# board.net
KiCad netlist of a schematic drawn in EAGLE
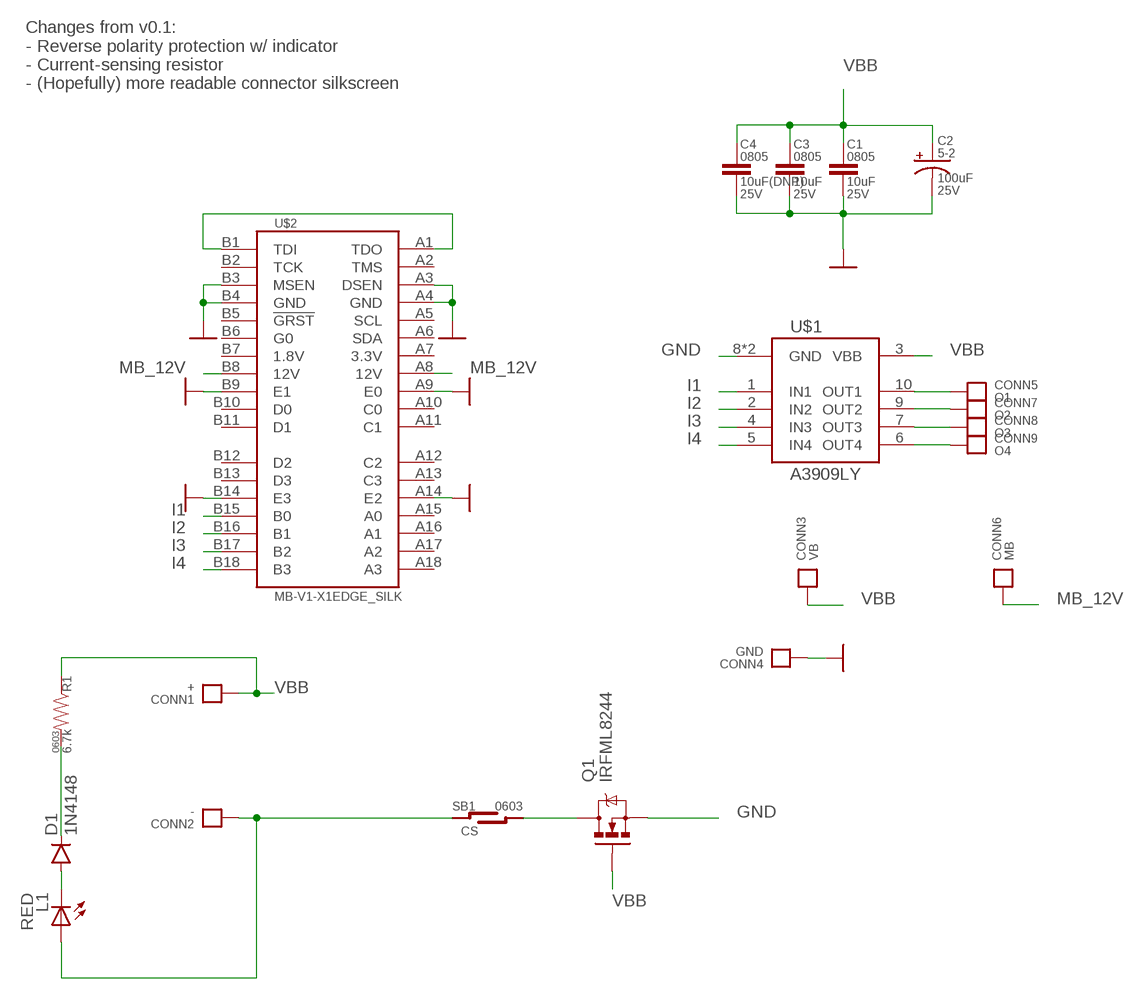
[diagram p0: schematic, sheet 1]

(export (version "E")
  (design (tool "Eeschema 10.0.6"))
  (components
    (comp (ref "C1")
      (value "10uF")
      (footprint "eagle-import:0805-CAP")
      (fields (field (name "VOLTAGE") "6.3V") (field (name "VOLTAGE_1") "25V"))
      (libsource (lib "eagle-import") (part "CAP0805"))
    )
    (comp (ref "C2")
      (value "100uF")
      (footprint "eagle-import:CAP-5-2")
      (fields (field (name "VOLTAGE") "6.3V") (field (name "VOLTAGE_1") "25V"))
      (libsource (lib "eagle-import") (part "CAP_POLPTH-5-2"))
    )
    (comp (ref "C3")
      (value "10uF")
      (footprint "eagle-import:0805-CAP")
      (fields (field (name "VOLTAGE") "6.3V") (field (name "VOLTAGE_1") "25V"))
      (libsource (lib "eagle-import") (part "CAP0805"))
    )
    (comp (ref "C4")
      (value "10uF(DNP)")
      (footprint "eagle-import:0805-CAP")
      (fields (field (name "VOLTAGE") "6.3V") (field (name "VOLTAGE_1") "25V"))
      (libsource (lib "eagle-import") (part "CAP0805"))
    )
    (comp (ref "CONN1")
      (value "+")
      (footprint "eagle-import:SCREW_5MM")
      (libsource (lib "eagle-import") (part "CONNECTORSCREW_5MM"))
    )
    (comp (ref "CONN2")
      (value "-")
      (footprint "eagle-import:SCREW_5MM")
      (libsource (lib "eagle-import") (part "CONNECTORSCREW_5MM"))
    )
    (comp (ref "CONN3")
      (value "VB")
      (footprint "eagle-import:SCREW_2.5MM")
      (libsource (lib "eagle-import") (part "CONNECTORSCREW_2.5MM"))
    )
    (comp (ref "CONN4")
      (value "GND")
      (footprint "eagle-import:SCREW_2.5MM")
      (libsource (lib "eagle-import") (part "CONNECTORSCREW_2.5MM"))
    )
    (comp (ref "CONN5")
      (value "O1")
      (footprint "eagle-import:SCREW_2.5MM")
      (libsource (lib "eagle-import") (part "CONNECTORSCREW_2.5MM"))
    )
    (comp (ref "CONN6")
      (value "MB")
      (footprint "eagle-import:SCREW_2.5MM")
      (libsource (lib "eagle-import") (part "CONNECTORSCREW_2.5MM"))
    )
    (comp (ref "CONN7")
      (value "O2")
      (footprint "eagle-import:SCREW_2.5MM")
      (libsource (lib "eagle-import") (part "CONNECTORSCREW_2.5MM"))
    )
    (comp (ref "CONN8")
      (value "O3")
      (footprint "eagle-import:SCREW_2.5MM")
      (libsource (lib "eagle-import") (part "CONNECTORSCREW_2.5MM"))
    )
    (comp (ref "CONN9")
      (value "O4")
      (footprint "eagle-import:SCREW_2.5MM")
      (libsource (lib "eagle-import") (part "CONNECTORSCREW_2.5MM"))
    )
    (comp (ref "D1")
      (value "1N4148")
      (footprint "eagle-import:SOD-323")
      (libsource (lib "eagle-import") (part "DIODESOD"))
    )
    (comp (ref "L1")
      (value "RED")
      (footprint "eagle-import:0603_LED")
      (libsource (lib "eagle-import") (part "LED0603"))
    )
    (comp (ref "Q1")
      (value "IRFML8244")
      (footprint "eagle-import:SOT23")
      (libsource (lib "eagle-import") (part "MOSFET-NCHANNELBSS138"))
    )
    (comp (ref "R1")
      (value "6.7k")
      (footprint "eagle-import:0603-RES")
      (libsource (lib "eagle-import") (part "RESISTOR0603"))
    )
    (comp (ref "SB1")
      (value "CS")
      (footprint "eagle-import:SB-0603")
      (libsource (lib "eagle-import") (part "SOLDER-BRIDGE0603"))
    )
    (comp (ref "U$1")
      (value "A3909LY")
      (footprint "eagle-import:MSOP10")
      (libsource (lib "eagle-import") (part "A3909LY"))
    )
    (comp (ref "U$2")
      (value "MB-V1-X1EDGE_SILK")
      (footprint "eagle-import:MB-V1-X1-EDGE")
      (libsource (lib "eagle-import") (part "MB-V1-X1EDGE_SILK"))
    )
  )
  (nets
    (net (code "1") (name "/I1") (class "Default")
      (node (ref "U$1") (pin "1") (pinfunction "IN1_1") (pintype "bidirectional"))
      (node (ref "U$2") (pin "B15") (pinfunction "B0_B15") (pintype "bidirectional"))
    )
    (net (code "2") (name "/I2") (class "Default")
      (node (ref "U$1") (pin "2") (pinfunction "IN2_2") (pintype "bidirectional"))
      (node (ref "U$2") (pin "B16") (pinfunction "B1_B16") (pintype "bidirectional"))
    )
    (net (code "3") (name "/I3") (class "Default")
      (node (ref "U$1") (pin "4") (pinfunction "IN3_4") (pintype "bidirectional"))
      (node (ref "U$2") (pin "B17") (pinfunction "B2_B17") (pintype "bidirectional"))
    )
    (net (code "4") (name "/I4") (class "Default")
      (node (ref "U$1") (pin "5") (pinfunction "IN4_5") (pintype "bidirectional"))
      (node (ref "U$2") (pin "B18") (pinfunction "B3_B18") (pintype "bidirectional"))
    )
    (net (code "5") (name "/MB_12V") (class "Default")
      (node (ref "CONN6") (pin "P") (pinfunction "P_P") (pintype "bidirectional"))
      (node (ref "U$2") (pin "A8") (pinfunction "12V_A8") (pintype "bidirectional"))
      (node (ref "U$2") (pin "B8") (pinfunction "12V_B8") (pintype "bidirectional"))
    )
    (net (code "6") (name "/VBB") (class "Default")
      (node (ref "C1") (pin "1") (pinfunction "1_1") (pintype "passive"))
      (node (ref "C2") (pin "1") (pinfunction "+_1") (pintype "passive"))
      (node (ref "C3") (pin "1") (pinfunction "1_1") (pintype "passive"))
      (node (ref "C4") (pin "1") (pinfunction "1_1") (pintype "passive"))
      (node (ref "CONN1") (pin "P$1") (pinfunction "P_P$1") (pintype "bidirectional"))
      (node (ref "CONN3") (pin "P") (pinfunction "P_P") (pintype "bidirectional"))
      (node (ref "Q1") (pin "1") (pinfunction "G_1") (pintype "passive"))
      (node (ref "R1") (pin "1") (pinfunction "1_1") (pintype "passive"))
      (node (ref "U$1") (pin "3") (pinfunction "VBB_3") (pintype "input"))
    )
    (net (code "7") (name "GND") (class "Default")
      (node (ref "C1") (pin "2") (pinfunction "2_2") (pintype "passive"))
      (node (ref "C2") (pin "2") (pinfunction "-_2") (pintype "passive"))
      (node (ref "C3") (pin "2") (pinfunction "2_2") (pintype "passive"))
      (node (ref "C4") (pin "2") (pinfunction "2_2") (pintype "passive"))
      (node (ref "CONN4") (pin "P") (pinfunction "P_P") (pintype "bidirectional"))
      (node (ref "Q1") (pin "2") (pinfunction "S_2") (pintype "passive"))
      (node (ref "U$1") (pin "8") (pinfunction "GND_8") (pintype "input"))
      (node (ref "U$1") (pin "PAD") (pinfunction "GND_PAD") (pintype "input"))
      (node (ref "U$2") (pin "A14") (pinfunction "E2_A14") (pintype "bidirectional"))
      (node (ref "U$2") (pin "A3") (pinfunction "DSEN_A3") (pintype "bidirectional"))
      (node (ref "U$2") (pin "A4") (pinfunction "GND_A4") (pintype "input"))
      (node (ref "U$2") (pin "A9") (pinfunction "E0_A9") (pintype "bidirectional"))
      (node (ref "U$2") (pin "B14") (pinfunction "E3_B14") (pintype "bidirectional"))
      (node (ref "U$2") (pin "B3") (pinfunction "MSEN_B3") (pintype "bidirectional"))
      (node (ref "U$2") (pin "B4") (pinfunction "GND_B4") (pintype "input"))
      (node (ref "U$2") (pin "B9") (pinfunction "E1_B9") (pintype "bidirectional"))
    )
    (net (code "8") (name "Net-(CONN2-P)") (class "Default")
      (node (ref "CONN2") (pin "P$1") (pinfunction "P_P$1") (pintype "bidirectional"))
      (node (ref "L1") (pin "A") (pinfunction "A_A") (pintype "passive"))
      (node (ref "SB1") (pin "L1") (pinfunction "P$1_L1") (pintype "passive"))
      (node (ref "SB1") (pin "L2") (pinfunction "P$1_L2") (pintype "passive"))
    )
    (net (code "9") (name "Net-(D1-PadA)") (class "Default")
      (node (ref "D1") (pin "A") (pinfunction "A_A") (pintype "passive"))
      (node (ref "L1") (pin "C") (pinfunction "C_C") (pintype "passive"))
    )
    (net (code "10") (name "Net-(D1-PadC)") (class "Default")
      (node (ref "D1") (pin "C") (pinfunction "C_C") (pintype "passive"))
      (node (ref "R1") (pin "2") (pinfunction "2_2") (pintype "passive"))
    )
    (net (code "11") (name "Net-(Q1-D)") (class "Default")
      (node (ref "Q1") (pin "3") (pinfunction "D_3") (pintype "passive"))
      (node (ref "SB1") (pin "R1") (pinfunction "P$2_R1") (pintype "passive"))
      (node (ref "SB1") (pin "R2") (pinfunction "P$2_R2") (pintype "passive"))
    )
    (net (code "12") (name "Net-(U$1-OUT1)") (class "Default")
      (node (ref "CONN5") (pin "P") (pinfunction "P_P") (pintype "bidirectional"))
      (node (ref "U$1") (pin "10") (pinfunction "OUT1_10") (pintype "output"))
    )
    (net (code "13") (name "Net-(U$1-OUT2)") (class "Default")
      (node (ref "CONN7") (pin "P") (pinfunction "P_P") (pintype "bidirectional"))
      (node (ref "U$1") (pin "9") (pinfunction "OUT2_9") (pintype "output"))
    )
    (net (code "14") (name "Net-(U$1-OUT3)") (class "Default")
      (node (ref "CONN8") (pin "P") (pinfunction "P_P") (pintype "bidirectional"))
      (node (ref "U$1") (pin "7") (pinfunction "OUT3_7") (pintype "output"))
    )
    (net (code "15") (name "Net-(U$1-OUT4)") (class "Default")
      (node (ref "CONN9") (pin "P") (pinfunction "P_P") (pintype "bidirectional"))
      (node (ref "U$1") (pin "6") (pinfunction "OUT4_6") (pintype "output"))
    )
    (net (code "16") (name "Net-(U$2-TDI)") (class "Default")
      (node (ref "U$2") (pin "A1") (pinfunction "TDO_A1") (pintype "bidirectional"))
      (node (ref "U$2") (pin "B1") (pinfunction "TDI_B1") (pintype "bidirectional"))
    )
    (net (code "17") (name "unconnected-(U$2-1.8V-PadB7)") (class "Default")
      (node (ref "U$2") (pin "B7") (pinfunction "1.8V_B7") (pintype "bidirectional"))
    )
    (net (code "18") (name "unconnected-(U$2-3.3V-PadA7)") (class "Default")
      (node (ref "U$2") (pin "A7") (pinfunction "3.3V_A7") (pintype "bidirectional"))
    )
    (net (code "19") (name "unconnected-(U$2-A0-PadA15)") (class "Default")
      (node (ref "U$2") (pin "A15") (pinfunction "A0_A15") (pintype "bidirectional"))
    )
    (net (code "20") (name "unconnected-(U$2-A1-PadA16)") (class "Default")
      (node (ref "U$2") (pin "A16") (pinfunction "A1_A16") (pintype "bidirectional"))
    )
    (net (code "21") (name "unconnected-(U$2-A2-PadA17)") (class "Default")
      (node (ref "U$2") (pin "A17") (pinfunction "A2_A17") (pintype "bidirectional"))
    )
    (net (code "22") (name "unconnected-(U$2-A3-PadA18)") (class "Default")
      (node (ref "U$2") (pin "A18") (pinfunction "A3_A18") (pintype "bidirectional"))
    )
    (net (code "23") (name "unconnected-(U$2-C0-PadA10)") (class "Default")
      (node (ref "U$2") (pin "A10") (pinfunction "C0_A10") (pintype "bidirectional"))
    )
    (net (code "24") (name "unconnected-(U$2-C1-PadA11)") (class "Default")
      (node (ref "U$2") (pin "A11") (pinfunction "C1_A11") (pintype "bidirectional"))
    )
    (net (code "25") (name "unconnected-(U$2-C2-PadA12)") (class "Default")
      (node (ref "U$2") (pin "A12") (pinfunction "C2_A12") (pintype "bidirectional"))
    )
    (net (code "26") (name "unconnected-(U$2-C3-PadA13)") (class "Default")
      (node (ref "U$2") (pin "A13") (pinfunction "C3_A13") (pintype "bidirectional"))
    )
    (net (code "27") (name "unconnected-(U$2-D0-PadB10)") (class "Default")
      (node (ref "U$2") (pin "B10") (pinfunction "D0_B10") (pintype "bidirectional"))
    )
    (net (code "28") (name "unconnected-(U$2-D1-PadB11)") (class "Default")
      (node (ref "U$2") (pin "B11") (pinfunction "D1_B11") (pintype "bidirectional"))
    )
    (net (code "29") (name "unconnected-(U$2-D2-PadB12)") (class "Default")
      (node (ref "U$2") (pin "B12") (pinfunction "D2_B12") (pintype "bidirectional"))
    )
    (net (code "30") (name "unconnected-(U$2-D3-PadB13)") (class "Default")
      (node (ref "U$2") (pin "B13") (pinfunction "D3_B13") (pintype "bidirectional"))
    )
    (net (code "31") (name "unconnected-(U$2-G0-PadB6)") (class "Default")
      (node (ref "U$2") (pin "B6") (pinfunction "G0_B6") (pintype "bidirectional"))
    )
    (net (code "32") (name "unconnected-(U$2-SCL-PadA5)") (class "Default")
      (node (ref "U$2") (pin "A5") (pinfunction "SCL_A5") (pintype "bidirectional"))
    )
    (net (code "33") (name "unconnected-(U$2-SDA-PadA6)") (class "Default")
      (node (ref "U$2") (pin "A6") (pinfunction "SDA_A6") (pintype "bidirectional"))
    )
    (net (code "34") (name "unconnected-(U$2-TCK-PadB2)") (class "Default")
      (node (ref "U$2") (pin "B2") (pinfunction "TCK_B2") (pintype "bidirectional"))
    )
    (net (code "35") (name "unconnected-(U$2-TMS-PadA2)") (class "Default")
      (node (ref "U$2") (pin "A2") (pinfunction "TMS_A2") (pintype "bidirectional"))
    )
    (net (code "36") (name "unconnected-(U$2-~{GRST}-PadB5)") (class "Default")
      (node (ref "U$2") (pin "B5") (pinfunction "~{GRST}_B5") (pintype "bidirectional"))
    )
  )
)
